# Ring_wearable_ver3_4.net
KiCad netlist of a schematic drawn in Altium Designer
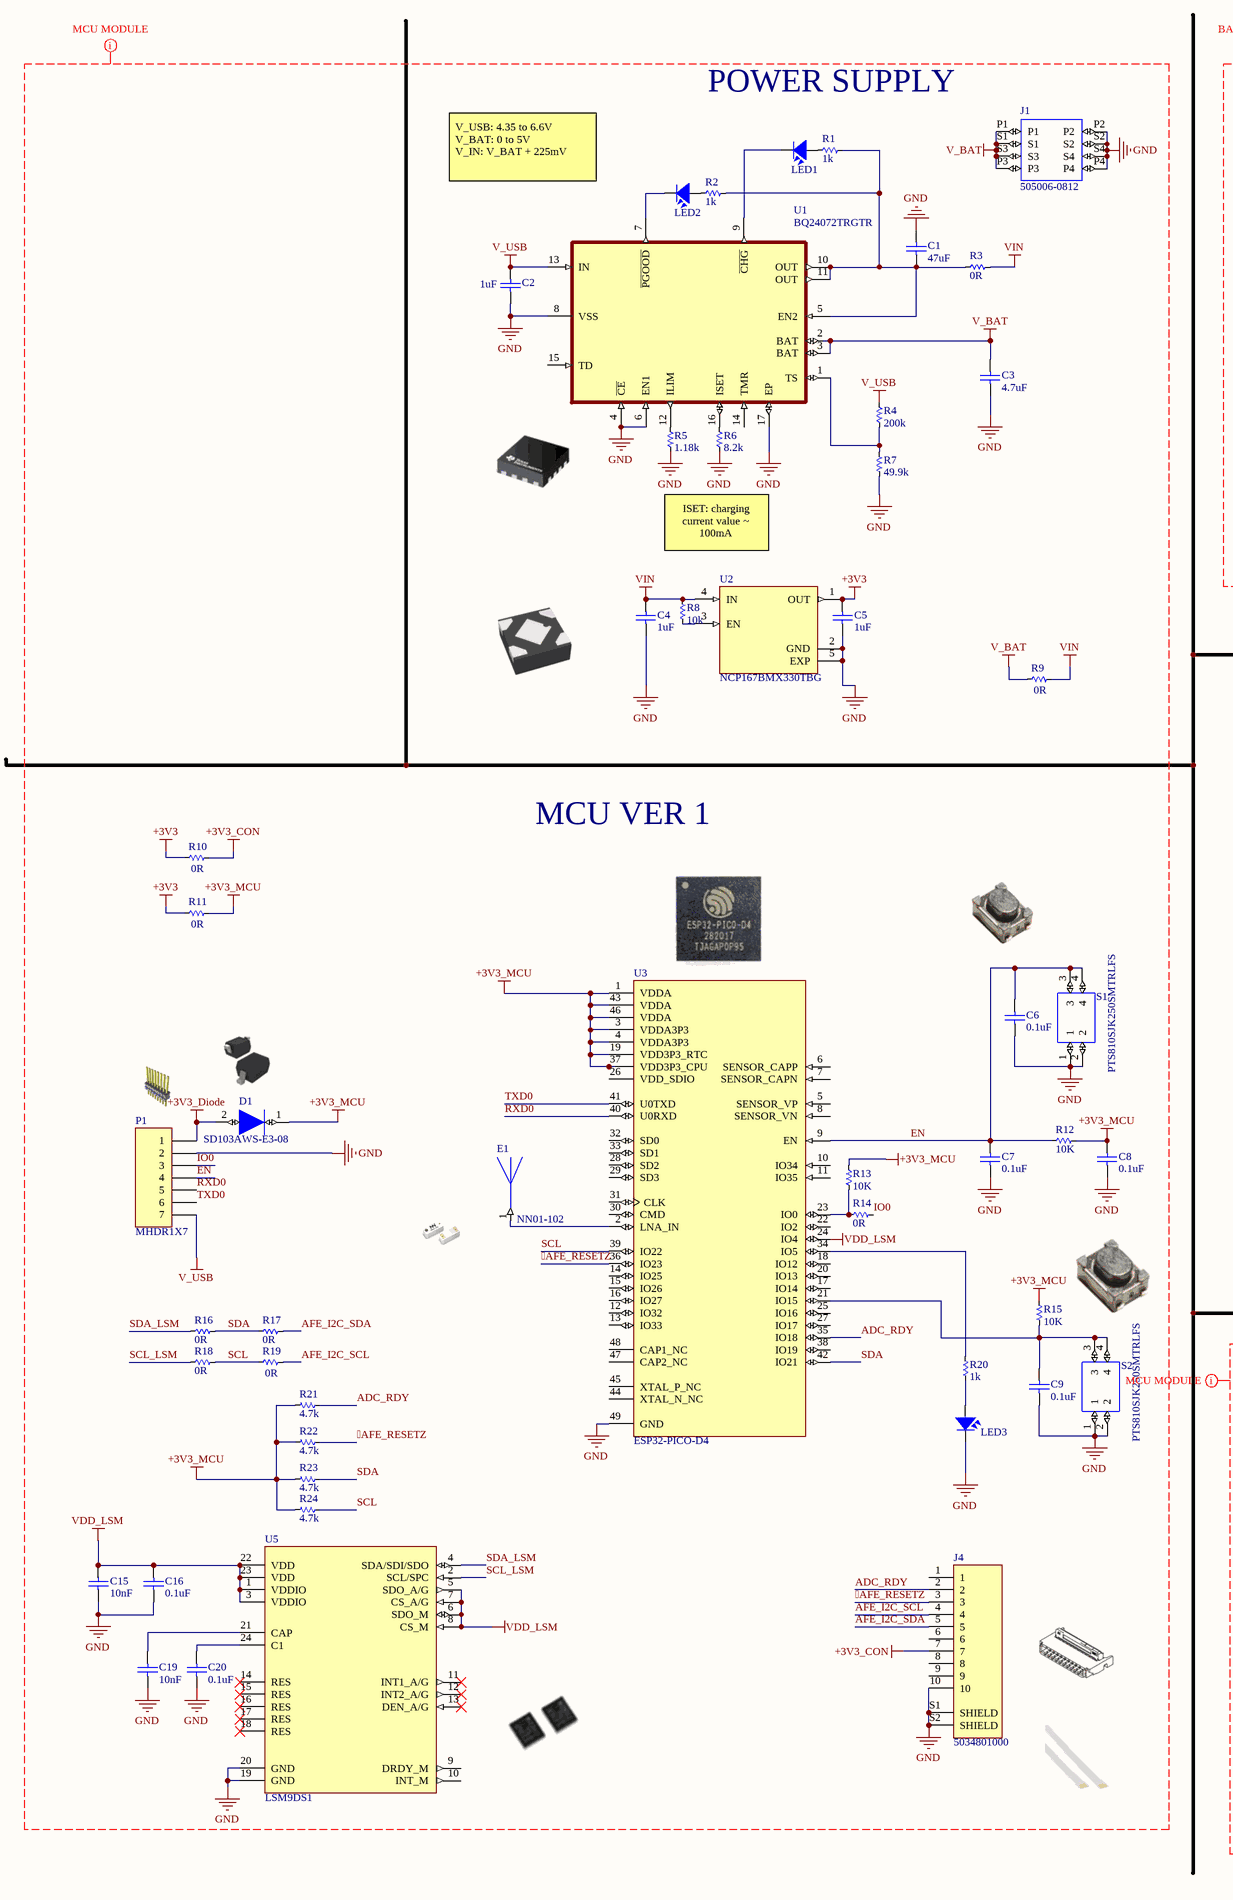
[diagram p0: Ring_wearable_ver3.4.SchDoc, left]
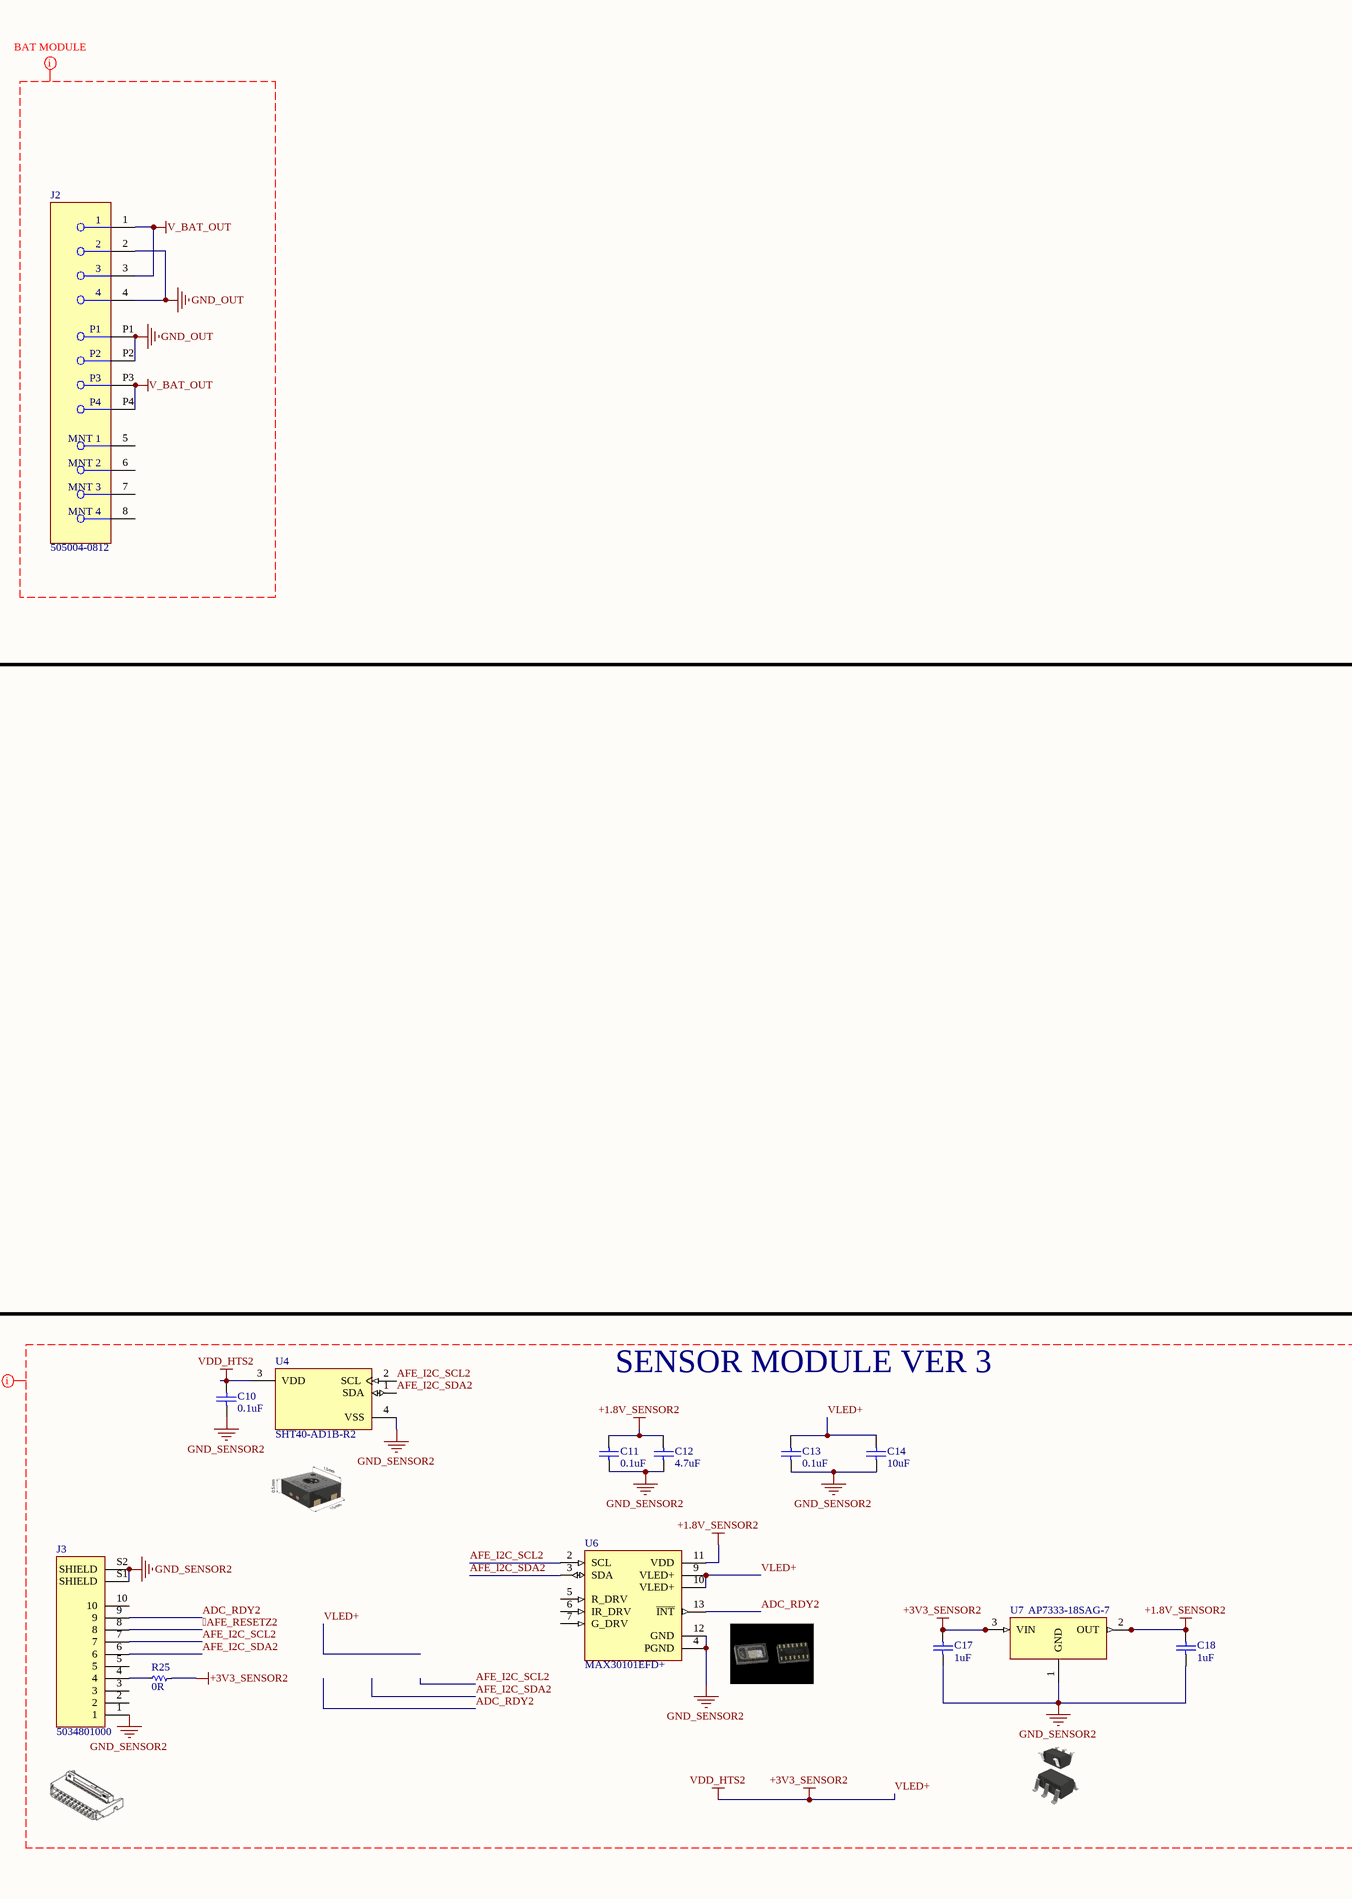
[diagram p1: Ring_wearable_ver3.4.SchDoc, right]

(export (version "E")
  (design (tool "Eeschema 10.0.6"))
  (components
    (comp (ref "C1")
      (value "4.7uF")
      (footprint "RES-SMD-0402")
      (description "Capacitor")
      (fields (field (name "ALTIUM_UNNAMED_1") "47uF") (field (name "PUBLISHER") "Altium Limited"))
      (libsource (lib "Miscellaneous Devices") (part "Cap"))
    )
    (comp (ref "C2")
      (value "1uF")
      (footprint "RES-SMD-0402")
      (description "Capacitor")
      (fields (field (name "ALTIUM_UNNAMED_1") "1uF") (field (name "PUBLISHER") "Altium Limited"))
      (libsource (lib "Miscellaneous Devices") (part "Cap"))
    )
    (comp (ref "C3")
      (value "4.7uF")
      (footprint "RES-SMD-0402")
      (description "Capacitor")
      (fields (field (name "ALTIUM_UNNAMED_1") "4.7uF") (field (name "PUBLISHER") "Altium Limited"))
      (libsource (lib "Miscellaneous Devices") (part "Cap"))
    )
    (comp (ref "C4")
      (value "1uF")
      (footprint "RES-SMD-0402")
      (description "Capacitor")
      (fields (field (name "ALTIUM_UNNAMED_1") "1uF") (field (name "PUBLISHER") "Altium Limited"))
      (libsource (lib "Miscellaneous Devices") (part "Cap"))
    )
    (comp (ref "C5")
      (value "1uF")
      (footprint "RES-SMD-0402")
      (description "Capacitor")
      (fields (field (name "ALTIUM_UNNAMED_1") "1uF") (field (name "PUBLISHER") "Altium Limited"))
      (libsource (lib "Miscellaneous Devices") (part "Cap"))
    )
    (comp (ref "C6")
      (value "0.1uF")
      (footprint "RES-SMD-0402")
      (description "Capacitor")
      (fields (field (name "ALTIUM_UNNAMED_1") "0.1uF") (field (name "PUBLISHER") "Altium Limited"))
      (libsource (lib "Miscellaneous Devices") (part "Cap"))
    )
    (comp (ref "C7")
      (value "0.1uF")
      (footprint "RES-SMD-0603")
      (description "Capacitor")
      (fields (field (name "ALTIUM_UNNAMED_1") "0.1uF") (field (name "PUBLISHER") "Altium Limited"))
      (libsource (lib "Miscellaneous Devices") (part "Cap"))
    )
    (comp (ref "C8")
      (value "0.1uF")
      (footprint "RES-SMD-0402")
      (description "Capacitor")
      (fields (field (name "ALTIUM_UNNAMED_1") "0.1uF") (field (name "PUBLISHER") "Altium Limited"))
      (libsource (lib "Miscellaneous Devices") (part "Cap"))
    )
    (comp (ref "C9")
      (value "0.1uF")
      (footprint "RES-SMD-0402")
      (description "Capacitor")
      (fields (field (name "ALTIUM_UNNAMED_1") "0.1uF") (field (name "PUBLISHER") "Altium Limited"))
      (libsource (lib "Miscellaneous Devices") (part "Cap"))
    )
    (comp (ref "C10")
      (value "0.1uF")
      (footprint "RES-SMD-0402")
      (description "Capacitor")
      (fields (field (name "ALTIUM_UNNAMED_1") "0.1uF") (field (name "PUBLISHER") "Altium Limited"))
      (libsource (lib "Miscellaneous Devices") (part "Cap"))
    )
    (comp (ref "C11")
      (value "0.1uF")
      (footprint "RES-SMD-0402")
      (description "Capacitor")
      (fields (field (name "ALTIUM_UNNAMED_1") "0.1uF") (field (name "PUBLISHER") "Altium Limited"))
      (libsource (lib "Miscellaneous Devices") (part "Cap"))
    )
    (comp (ref "C12")
      (value "4.7uF")
      (footprint "RES-SMD-0402")
      (description "Capacitor")
      (fields (field (name "ALTIUM_UNNAMED_1") "4.7uF") (field (name "PUBLISHER") "Altium Limited"))
      (libsource (lib "Miscellaneous Devices") (part "Cap"))
    )
    (comp (ref "C13")
      (value "0.1uF")
      (footprint "RES-SMD-0402")
      (description "Capacitor")
      (fields (field (name "ALTIUM_UNNAMED_1") "0.1uF") (field (name "PUBLISHER") "Altium Limited"))
      (libsource (lib "Miscellaneous Devices") (part "Cap"))
    )
    (comp (ref "C14")
      (value "10uF")
      (footprint "RES-SMD-0402")
      (description "Capacitor")
      (fields (field (name "ALTIUM_UNNAMED_1") "10uF") (field (name "PUBLISHER") "Altium Limited"))
      (libsource (lib "Miscellaneous Devices") (part "Cap"))
    )
    (comp (ref "C15")
      (value "10nF")
      (footprint "RES-SMD-0402")
      (description "Capacitor")
      (fields (field (name "ALTIUM_UNNAMED_1") "10nF") (field (name "PUBLISHER") "Altium Limited"))
      (libsource (lib "Miscellaneous Devices") (part "Cap"))
    )
    (comp (ref "C16")
      (value "0.1uF")
      (footprint "RES-SMD-0402")
      (description "Capacitor")
      (fields (field (name "ALTIUM_UNNAMED_1") "0.1uF") (field (name "PUBLISHER") "Altium Limited"))
      (libsource (lib "Miscellaneous Devices") (part "Cap"))
    )
    (comp (ref "C17")
      (value "1uF")
      (footprint "RES-SMD-0402")
      (description "Capacitor")
      (fields (field (name "ALTIUM_UNNAMED_1") "1uF") (field (name "PUBLISHER") "Altium Limited"))
      (libsource (lib "Miscellaneous Devices") (part "Cap"))
    )
    (comp (ref "C18")
      (value "1uF")
      (footprint "RES-SMD-0402")
      (description "Capacitor")
      (fields (field (name "ALTIUM_UNNAMED_1") "1uF") (field (name "PUBLISHER") "Altium Limited"))
      (libsource (lib "Miscellaneous Devices") (part "Cap"))
    )
    (comp (ref "C19")
      (value "10nF")
      (footprint "RES-SMD-0402")
      (description "Capacitor")
      (fields (field (name "ALTIUM_UNNAMED_1") "10nF") (field (name "PUBLISHER") "Altium Limited"))
      (libsource (lib "Miscellaneous Devices") (part "Cap"))
    )
    (comp (ref "C20")
      (value "0.1uF")
      (footprint "RES-SMD-0402")
      (description "Capacitor")
      (fields (field (name "ALTIUM_UNNAMED_1") "0.1uF") (field (name "PUBLISHER") "Altium Limited"))
      (libsource (lib "Miscellaneous Devices") (part "Cap"))
    )
    (comp (ref "D1")
      (value "SD103AWS-E3-08")
      (footprint "SOD2713X115N")
      (fields (field (name "MF") "Vishay") (field (name "DIGI-KEY_PART_NUMBER") "SD103AWS-E3-08GITR-ND"))
      (libsource (lib "SD103AWS-E3-08") (part "SD103AWS-E3-08"))
    )
    (comp (ref "E1")
      (value "NN01-102")
      (footprint "XCVR_NN01-102")
      (description "2.45GHz Bluetooth, WLAN, Zigbeeâ„¢ Chip RF Antenna 2.4GHz ~ 2.5GHz 1.7dBi Solder Surface Mount")
      (fields (field (name "MF") "Ignion"))
      (libsource (lib "NN01-102") (part "NN01-102"))
    )
    (comp (ref "J1")
      (value "505006-0812")
      (footprint "5050060812:5050060812")
      (description "8 (4 + 4 Power) Position Connector Plug, Outer Shroud Contacts Surface Mount Gold")
      (fields (field (name "MF") "Molex"))
      (libsource (lib "505006-0812") (part "505006-0812"))
    )
    (comp (ref "J2")
      (value "505004-0812")
      (footprint "FP-505004-0812-MFG")
      (description "CONN RCPT 4POS SMD GOLD")
      (libsource (lib "Altium Content Vault") (part "23163b8db27f5e4a30e89b4e86b5801"))
    )
    (comp (ref "J3")
      (value "5034801000")
      (footprint "MOLEX_5034801000")
      (description "10 Position FFC, FPC Connector Contacts, Top and Bottom 0.020 _0.50mm_ Surface Mount, Right Angle")
      (fields (field (name "MF") "Molex") (field (name "DIGI-KEY_PART_NUMBER") "WM1389CT-ND"))
      (libsource (lib "") (part "5034801000_1"))
    )
    (comp (ref "J4")
      (value "5034801000")
      (footprint "MOLEX_5034801000")
      (description "10 Position FFC, FPC Connector Contacts, Top and Bottom 0.020 _0.50mm_ Surface Mount, Right Angle")
      (fields (field (name "MF") "Molex") (field (name "DIGI-KEY_PART_NUMBER") "WM1389CT-ND"))
      (libsource (lib "5034801000") (part "5034801000"))
    )
    (comp (ref "LED1")
      (value "LED_INDICATE1")
      (footprint "LED-0402")
      (description "LED Single colour Green and Red")
      (libsource (lib "LIBRARY") (part "LED"))
    )
    (comp (ref "LED2")
      (value "LED_INDICATE2")
      (footprint "LED-0402")
      (description "LED Single colour Green and Red")
      (libsource (lib "LIBRARY") (part "LED"))
    )
    (comp (ref "LED3")
      (value "LED_INDICATE3")
      (footprint "LED-0402")
      (description "LED Single colour Green and Red")
      (libsource (lib "LIBRARY") (part "LED"))
    )
    (comp (ref "P1")
      (value "MHDR1X7")
      (footprint "MHDR1X7")
      (description "Header, 7-Pin")
      (fields (field (name "PUBLISHER") "Altium Limited"))
      (libsource (lib "Miscellaneous Connectors") (part "MHDR1X7"))
    )
    (comp (ref "R1")
      (value "1k")
      (footprint "RES-SMD-0402")
      (description "Resistor")
      (fields
        (field (name "MANUFACTURER") "Generic Components")
        (field (name "PUBLISHER") "Altium Hobart Technology Centre")
      )
      (libsource (lib "LIBRARY") (part "Res-SMD"))
    )
    (comp (ref "R2")
      (value "1k")
      (footprint "RES-SMD-0402")
      (description "Resistor")
      (fields
        (field (name "MANUFACTURER") "Generic Components")
        (field (name "PUBLISHER") "Altium Hobart Technology Centre")
      )
      (libsource (lib "LIBRARY") (part "Res-SMD"))
    )
    (comp (ref "R3")
      (value "0R")
      (footprint "RES-SMD-0402")
      (description "Resistor")
      (fields
        (field (name "MANUFACTURER") "Generic Components")
        (field (name "PUBLISHER") "Altium Hobart Technology Centre")
      )
      (libsource (lib "LIBRARY") (part "Res-SMD"))
    )
    (comp (ref "R4")
      (value "200k")
      (footprint "RES-SMD-0402")
      (description "Resistor")
      (fields
        (field (name "MANUFACTURER") "Generic Components")
        (field (name "PUBLISHER") "Altium Hobart Technology Centre")
      )
      (libsource (lib "LIBRARY") (part "Res-SMD"))
    )
    (comp (ref "R5")
      (value "1.18k")
      (footprint "RES-SMD-0402")
      (description "Resistor")
      (fields
        (field (name "MANUFACTURER") "Generic Components")
        (field (name "PUBLISHER") "Altium Hobart Technology Centre")
      )
      (libsource (lib "LIBRARY") (part "Res-SMD"))
    )
    (comp (ref "R6")
      (value "8.2k")
      (footprint "RES-SMD-0402")
      (description "Resistor")
      (fields
        (field (name "MANUFACTURER") "Generic Components")
        (field (name "PUBLISHER") "Altium Hobart Technology Centre")
      )
      (libsource (lib "LIBRARY") (part "Res-SMD"))
    )
    (comp (ref "R7")
      (value "49.9k")
      (footprint "RES-SMD-0402")
      (description "Resistor")
      (fields
        (field (name "MANUFACTURER") "Generic Components")
        (field (name "PUBLISHER") "Altium Hobart Technology Centre")
      )
      (libsource (lib "LIBRARY") (part "Res-SMD"))
    )
    (comp (ref "R8")
      (value "10k")
      (footprint "RES-SMD-0402")
      (description "Resistor")
      (fields
        (field (name "MANUFACTURER") "Generic Components")
        (field (name "PUBLISHER") "Altium Hobart Technology Centre")
      )
      (libsource (lib "LIBRARY") (part "Res-SMD"))
    )
    (comp (ref "R9")
      (value "0R")
      (footprint "RES-SMD-0402")
      (description "Resistor")
      (fields
        (field (name "MANUFACTURER") "Generic Components")
        (field (name "PUBLISHER") "Altium Hobart Technology Centre")
      )
      (libsource (lib "LIBRARY") (part "Res-SMD"))
    )
    (comp (ref "R10")
      (value "0R")
      (footprint "RES-SMD-0402")
      (description "Resistor")
      (fields
        (field (name "MANUFACTURER") "Generic Components")
        (field (name "PUBLISHER") "Altium Hobart Technology Centre")
      )
      (libsource (lib "LIBRARY") (part "Res-SMD"))
    )
    (comp (ref "R11")
      (value "0R")
      (footprint "RES-SMD-0402")
      (description "Resistor")
      (fields
        (field (name "MANUFACTURER") "Generic Components")
        (field (name "PUBLISHER") "Altium Hobart Technology Centre")
      )
      (libsource (lib "LIBRARY") (part "Res-SMD"))
    )
    (comp (ref "R12")
      (value "10K")
      (footprint "RES-SMD-0402")
      (description "Resistor")
      (fields
        (field (name "MANUFACTURER") "Generic Components")
        (field (name "PUBLISHER") "Altium Hobart Technology Centre")
      )
      (libsource (lib "LIBRARY") (part "Res-SMD"))
    )
    (comp (ref "R13")
      (value "10K")
      (footprint "RES-SMD-0603")
      (description "Resistor")
      (fields
        (field (name "MANUFACTURER") "Generic Components")
        (field (name "PUBLISHER") "Altium Hobart Technology Centre")
      )
      (libsource (lib "LIBRARY") (part "Res-SMD"))
    )
    (comp (ref "R14")
      (value "0R")
      (footprint "RES-SMD-0603")
      (description "Resistor")
      (fields
        (field (name "MANUFACTURER") "Generic Components")
        (field (name "PUBLISHER") "Altium Hobart Technology Centre")
      )
      (libsource (lib "LIBRARY") (part "Res-SMD"))
    )
    (comp (ref "R15")
      (value "10K")
      (footprint "RES-SMD-0402")
      (description "Resistor")
      (fields
        (field (name "MANUFACTURER") "Generic Components")
        (field (name "PUBLISHER") "Altium Hobart Technology Centre")
      )
      (libsource (lib "LIBRARY") (part "Res-SMD"))
    )
    (comp (ref "R16")
      (value "0R")
      (footprint "RES-SMD-0402")
      (description "Resistor")
      (fields
        (field (name "MANUFACTURER") "Generic Components")
        (field (name "PUBLISHER") "Altium Hobart Technology Centre")
      )
      (libsource (lib "LIBRARY") (part "Res-SMD"))
    )
    (comp (ref "R17")
      (value "0R")
      (footprint "RES-SMD-0402")
      (description "Resistor")
      (fields
        (field (name "MANUFACTURER") "Generic Components")
        (field (name "PUBLISHER") "Altium Hobart Technology Centre")
      )
      (libsource (lib "LIBRARY") (part "Res-SMD"))
    )
    (comp (ref "R18")
      (value "0R")
      (footprint "RES-SMD-0402")
      (description "Resistor")
      (fields
        (field (name "MANUFACTURER") "Generic Components")
        (field (name "PUBLISHER") "Altium Hobart Technology Centre")
      )
      (libsource (lib "LIBRARY") (part "Res-SMD"))
    )
    (comp (ref "R19")
      (value "0R")
      (footprint "RES-SMD-0402")
      (description "Resistor")
      (fields
        (field (name "MANUFACTURER") "Generic Components")
        (field (name "PUBLISHER") "Altium Hobart Technology Centre")
      )
      (libsource (lib "LIBRARY") (part "Res-SMD"))
    )
    (comp (ref "R20")
      (value "1k")
      (footprint "RES-SMD-0402")
      (description "Resistor")
      (fields
        (field (name "MANUFACTURER") "Generic Components")
        (field (name "PUBLISHER") "Altium Hobart Technology Centre")
      )
      (libsource (lib "LIBRARY") (part "Res-SMD"))
    )
    (comp (ref "R21")
      (value "4.7k")
      (footprint "RES-SMD-0402")
      (description "Resistor")
      (fields
        (field (name "MANUFACTURER") "Generic Components")
        (field (name "PUBLISHER") "Altium Hobart Technology Centre")
      )
      (libsource (lib "LIBRARY") (part "Res-SMD"))
    )
    (comp (ref "R22")
      (value "4.7k")
      (footprint "RES-SMD-0402")
      (description "Resistor")
      (fields
        (field (name "MANUFACTURER") "Generic Components")
        (field (name "PUBLISHER") "Altium Hobart Technology Centre")
      )
      (libsource (lib "LIBRARY") (part "Res-SMD"))
    )
    (comp (ref "R23")
      (value "4.7k")
      (footprint "RES-SMD-0402")
      (description "Resistor")
      (fields
        (field (name "MANUFACTURER") "Generic Components")
        (field (name "PUBLISHER") "Altium Hobart Technology Centre")
      )
      (libsource (lib "LIBRARY") (part "Res-SMD"))
    )
    (comp (ref "R24")
      (value "4.7k")
      (footprint "RES-SMD-0402")
      (description "Resistor")
      (fields
        (field (name "MANUFACTURER") "Generic Components")
        (field (name "PUBLISHER") "Altium Hobart Technology Centre")
      )
      (libsource (lib "LIBRARY") (part "Res-SMD"))
    )
    (comp (ref "R25")
      (value "0R")
      (footprint "RES-SMD-0402")
      (description "Resistor")
      (fields
        (field (name "MANUFACTURER") "Generic Components")
        (field (name "PUBLISHER") "Altium Hobart Technology Centre")
      )
      (libsource (lib "LIBRARY") (part "Res-SMD"))
    )
    (comp (ref "S1")
      (value "PTS810SJK250SMTRLFS")
      (footprint "PTS810SJG250SMTRLFS")
      (description "Tactile Switch SPST-NO Top Actuated Surface Mount")
      (fields (field (name "MF") "C&K"))
      (libsource (lib "PTS810SJK250SMTRLFS") (part "PTS810SJK250SMTRLFS"))
    )
    (comp (ref "S2")
      (value "PTS810SJK250SMTRLFS")
      (footprint "PTS810SJG250SMTRLFS")
      (description "Tactile Switch SPST-NO Top Actuated Surface Mount")
      (fields (field (name "MF") "C&K"))
      (libsource (lib "PTS810SJK250SMTRLFS") (part "PTS810SJK250SMTRLFS"))
    )
    (comp (ref "U1")
      (value "BQ24072TRGTR")
      (footprint "QFN50P300X300X100-17N")
      (fields (field (name "MF") "Texas Instruments"))
      (libsource (lib "BQ24072TRGTR") (part "BQ24072TRGTR"))
    )
    (comp (ref "U2")
      (value "NCP167BMX330TBG")
      (footprint "REG_NCP167BMX330TBG")
      (description "Linear Voltage Regulator IC 1 Output 700mA 4-XDFN _1x1_")
      (fields
        (field (name "DIGI-KEY_PART_NUMBER") "NCP167BMX330TBGOSCT-ND")
        (field (name "MF") "ON Semiconductor")
      )
      (libsource (lib "NCP167BMX330TBG") (part "NCP167BMX330TBG"))
    )
    (comp (ref "U3")
      (value "ESP32-PICO-D4")
      (footprint "PQFN50P700X700X104-49N")
      (libsource (lib "ESP32-PICO-D4") (part "ESP32-PICO-D4"))
    )
    (comp (ref "U4")
      (value "SHT40-AD1B-R2")
      (footprint "FP-SHT40-AD1B-R2-MFG")
      (description "SENSOR HUMIDITY 100 RH SMD")
      (libsource (lib "Altium Content Vault") (part "985d6b895d3abb4f56b1b691ea450a8"))
    )
    (comp (ref "U5")
      (value "LSM9DS1")
      (footprint "PQFN24P43_350X300X102L35X23N")
      (description "Accelerometer, Gyroscope, Magnetometer, Temperature, 9 Axis Sensor IÂ²C, SPI Output")
      (fields (field (name "MF") "STMicroelectronics"))
      (libsource (lib "LSM9DS1") (part "LSM9DS1"))
    )
    (comp (ref "U6")
      (value "MAX30101EFD+")
      (footprint "PSON80P330X560X165-14N")
      (description "Oximeter/Heart Rate Sensor IÂ²C Output")
      (fields (field (name "MF") "Maxim Integrated"))
      (libsource (lib "MAX30101EFD_") (part "MAX30101EFD+"))
    )
    (comp (ref "U7")
      (value "AP7333-18SAG-7")
      (footprint "SOT23-132")
      (libsource (lib "LIBRARY") (part "AP7370-18SA-7"))
    )
  )
  (nets
    (net (code "1") (name "+1.8V_SENSOR2") (class "Default")
      (node (ref "C11") (pin "1") (pinfunction "1_1") (pintype "passive"))
      (node (ref "C12") (pin "1") (pinfunction "1_1") (pintype "passive"))
      (node (ref "C18") (pin "1") (pinfunction "1_1") (pintype "passive"))
      (node (ref "U6") (pin "11") (pinfunction "VDD_11") (pintype "power_in"))
      (node (ref "U7") (pin "2") (pinfunction "OUT_2") (pintype "output"))
    )
    (net (code "2") (name "+3V3") (class "Default")
      (node (ref "C5") (pin "1") (pinfunction "1_1") (pintype "passive"))
      (node (ref "R10") (pin "2") (pinfunction "2_2") (pintype "passive"))
      (node (ref "R11") (pin "2") (pinfunction "2_2") (pintype "passive"))
      (node (ref "U2") (pin "1") (pinfunction "OUT_1") (pintype "output"))
    )
    (net (code "3") (name "+3V3_CON") (class "Default")
      (node (ref "J4") (pin "7") (pinfunction "7_7") (pintype "passive"))
      (node (ref "R10") (pin "1") (pinfunction "1_1") (pintype "passive"))
    )
    (net (code "4") (name "+3V3_Diode") (class "Default")
      (node (ref "D1") (pin "2") (pinfunction "A_2") (pintype "bidirectional"))
      (node (ref "P1") (pin "1") (pinfunction "1_1") (pintype "passive"))
    )
    (net (code "5") (name "+3V3_MCU") (class "Default")
      (node (ref "C8") (pin "1") (pinfunction "1_1") (pintype "passive"))
      (node (ref "D1") (pin "1") (pinfunction "K_1") (pintype "bidirectional"))
      (node (ref "R11") (pin "1") (pinfunction "1_1") (pintype "passive"))
      (node (ref "R12") (pin "1") (pinfunction "1_1") (pintype "passive"))
      (node (ref "R13") (pin "1") (pinfunction "1_1") (pintype "passive"))
      (node (ref "R15") (pin "1") (pinfunction "1_1") (pintype "passive"))
      (node (ref "R21") (pin "1") (pinfunction "1_1") (pintype "passive"))
      (node (ref "R22") (pin "1") (pinfunction "1_1") (pintype "passive"))
      (node (ref "R23") (pin "1") (pinfunction "1_1") (pintype "passive"))
      (node (ref "R24") (pin "1") (pinfunction "1_1") (pintype "passive"))
      (node (ref "U3") (pin "1") (pinfunction "VDDA_1") (pintype "power_in"))
      (node (ref "U3") (pin "19") (pinfunction "VDD3P3_RTC_19") (pintype "power_in"))
      (node (ref "U3") (pin "3") (pinfunction "VDDA3P3_3") (pintype "power_in"))
      (node (ref "U3") (pin "37") (pinfunction "VDD3P3_CPU_37") (pintype "power_in"))
      (node (ref "U3") (pin "4") (pinfunction "VDDA3P3_4") (pintype "power_in"))
      (node (ref "U3") (pin "43") (pinfunction "VDDA_43") (pintype "power_in"))
      (node (ref "U3") (pin "46") (pinfunction "VDDA_46") (pintype "power_in"))
    )
    (net (code "6") (name "+3V3_SENSOR2") (class "Default")
      (node (ref "C10") (pin "1") (pinfunction "1_1") (pintype "passive"))
      (node (ref "C13") (pin "1") (pinfunction "1_1") (pintype "passive"))
      (node (ref "C14") (pin "1") (pinfunction "1_1") (pintype "passive"))
      (node (ref "C17") (pin "1") (pinfunction "1_1") (pintype "passive"))
      (node (ref "R25") (pin "1") (pinfunction "1_1") (pintype "passive"))
      (node (ref "U4") (pin "3") (pinfunction "VDD_3") (pintype "power_in"))
      (node (ref "U6") (pin "10") (pinfunction "VLED+_10") (pintype "power_in"))
      (node (ref "U6") (pin "9") (pinfunction "VLED+_9") (pintype "power_in"))
      (node (ref "U7") (pin "3") (pinfunction "VIN_3") (pintype "input"))
    )
    (net (code "7") (name "/AFE_RESETZ") (class "Default")
      (node (ref "J4") (pin "3") (pinfunction "3_3") (pintype "passive"))
      (node (ref "R22") (pin "2") (pinfunction "2_2") (pintype "passive"))
      (node (ref "U3") (pin "36") (pinfunction "IO23_36") (pintype "bidirectional"))
    )
    (net (code "8") (name "/AFE_RESETZ2") (class "Default")
      (node (ref "J3") (pin "8") (pinfunction "8_8") (pintype "passive"))
    )
    (net (code "9") (name "/ADC_RDY") (class "Default")
      (node (ref "J4") (pin "2") (pinfunction "2_2") (pintype "passive"))
      (node (ref "R21") (pin "2") (pinfunction "2_2") (pintype "passive"))
      (node (ref "U3") (pin "35") (pinfunction "IO18_35") (pintype "bidirectional"))
    )
    (net (code "10") (name "/ADC_RDY2") (class "Default")
      (node (ref "J3") (pin "9") (pinfunction "9_9") (pintype "passive"))
      (node (ref "U6") (pin "13") (pinfunction "~{INT}_13") (pintype "output"))
    )
    (net (code "11") (name "/AFE_I2C_SCL") (class "Default")
      (node (ref "J4") (pin "4") (pinfunction "4_4") (pintype "passive"))
      (node (ref "R19") (pin "1") (pinfunction "1_1") (pintype "passive"))
    )
    (net (code "12") (name "/AFE_I2C_SCL2") (class "Default")
      (node (ref "J3") (pin "7") (pinfunction "7_7") (pintype "passive"))
      (node (ref "U4") (pin "2") (pinfunction "SCL_2") (pintype "input"))
      (node (ref "U6") (pin "2") (pinfunction "SCL_2") (pintype "input"))
    )
    (net (code "13") (name "/AFE_I2C_SDA") (class "Default")
      (node (ref "J4") (pin "5") (pinfunction "5_5") (pintype "passive"))
      (node (ref "R17") (pin "1") (pinfunction "1_1") (pintype "passive"))
    )
    (net (code "14") (name "/AFE_I2C_SDA2") (class "Default")
      (node (ref "J3") (pin "6") (pinfunction "6_6") (pintype "passive"))
      (node (ref "U4") (pin "1") (pinfunction "SDA_1") (pintype "bidirectional"))
      (node (ref "U6") (pin "3") (pinfunction "SDA_3") (pintype "bidirectional"))
    )
    (net (code "15") (name "/EN") (class "Default")
      (node (ref "C6") (pin "1") (pinfunction "1_1") (pintype "passive"))
      (node (ref "C7") (pin "1") (pinfunction "1_1") (pintype "passive"))
      (node (ref "P1") (pin "4") (pinfunction "4_4") (pintype "passive"))
      (node (ref "R12") (pin "2") (pinfunction "2_2") (pintype "passive"))
      (node (ref "S1") (pin "3") (pinfunction "3_3") (pintype "bidirectional"))
      (node (ref "S1") (pin "4") (pinfunction "4_4") (pintype "bidirectional"))
      (node (ref "U3") (pin "9") (pinfunction "EN_9") (pintype "input"))
    )
    (net (code "16") (name "/IO0") (class "Default")
      (node (ref "P1") (pin "3") (pinfunction "3_3") (pintype "passive"))
      (node (ref "R14") (pin "1") (pinfunction "1_1") (pintype "passive"))
    )
    (net (code "17") (name "/RXD0") (class "Default")
      (node (ref "P1") (pin "5") (pinfunction "5_5") (pintype "passive"))
      (node (ref "U3") (pin "40") (pinfunction "U0RXD_40") (pintype "bidirectional"))
    )
    (net (code "18") (name "/SCL") (class "Default")
      (node (ref "R18") (pin "1") (pinfunction "1_1") (pintype "passive"))
      (node (ref "R19") (pin "2") (pinfunction "2_2") (pintype "passive"))
      (node (ref "R24") (pin "2") (pinfunction "2_2") (pintype "passive"))
      (node (ref "U3") (pin "39") (pinfunction "IO22_39") (pintype "bidirectional"))
    )
    (net (code "19") (name "/SCL_LSM") (class "Default")
      (node (ref "R18") (pin "2") (pinfunction "2_2") (pintype "passive"))
      (node (ref "U5") (pin "2") (pinfunction "SCL/SPC_2") (pintype "input"))
    )
    (net (code "20") (name "/SDA") (class "Default")
      (node (ref "R16") (pin "1") (pinfunction "1_1") (pintype "passive"))
      (node (ref "R17") (pin "2") (pinfunction "2_2") (pintype "passive"))
      (node (ref "R23") (pin "2") (pinfunction "2_2") (pintype "passive"))
      (node (ref "U3") (pin "42") (pinfunction "IO21_42") (pintype "bidirectional"))
    )
    (net (code "21") (name "/SDA_LSM") (class "Default")
      (node (ref "R16") (pin "2") (pinfunction "2_2") (pintype "passive"))
      (node (ref "U5") (pin "4") (pinfunction "SDA/SDI/SDO_4") (pintype "bidirectional"))
    )
    (net (code "22") (name "/TXD0") (class "Default")
      (node (ref "P1") (pin "6") (pinfunction "6_6") (pintype "passive"))
      (node (ref "U3") (pin "41") (pinfunction "U0TXD_41") (pintype "bidirectional"))
    )
    (net (code "23") (name "GND") (class "Default")
      (node (ref "C1") (pin "1") (pinfunction "1_1") (pintype "passive"))
      (node (ref "C15") (pin "2") (pinfunction "2_2") (pintype "passive"))
      (node (ref "C16") (pin "2") (pinfunction "2_2") (pintype "passive"))
      (node (ref "C19") (pin "2") (pinfunction "2_2") (pintype "passive"))
      (node (ref "C2") (pin "1") (pinfunction "1_1") (pintype "passive"))
      (node (ref "C20") (pin "2") (pinfunction "2_2") (pintype "passive"))
      (node (ref "C3") (pin "2") (pinfunction "2_2") (pintype "passive"))
      (node (ref "C4") (pin "2") (pinfunction "2_2") (pintype "passive"))
      (node (ref "C5") (pin "2") (pinfunction "2_2") (pintype "passive"))
      (node (ref "C6") (pin "2") (pinfunction "2_2") (pintype "passive"))
      (node (ref "C7") (pin "2") (pinfunction "2_2") (pintype "passive"))
      (node (ref "C8") (pin "2") (pinfunction "2_2") (pintype "passive"))
      (node (ref "C9") (pin "2") (pinfunction "2_2") (pintype "passive"))
      (node (ref "J1") (pin "P2") (pinfunction "P2_P2") (pintype "bidirectional"))
      (node (ref "J1") (pin "P4") (pinfunction "P4_P4") (pintype "bidirectional"))
      (node (ref "J1") (pin "S2") (pinfunction "S2_S2") (pintype "bidirectional"))
      (node (ref "J1") (pin "S4") (pinfunction "S4_S4") (pintype "bidirectional"))
      (node (ref "J4") (pin "10") (pinfunction "10_10") (pintype "passive"))
      (node (ref "J4") (pin "S1") (pinfunction "SHIELD_S1") (pintype "passive"))
      (node (ref "J4") (pin "S2") (pinfunction "SHIELD_S2") (pintype "passive"))
      (node (ref "LED3") (pin "2") (pinfunction "2_2") (pintype "passive"))
      (node (ref "P1") (pin "2") (pinfunction "2_2") (pintype "passive"))
      (node (ref "R5") (pin "1") (pinfunction "1_1") (pintype "passive"))
      (node (ref "R6") (pin "1") (pinfunction "1_1") (pintype "passive"))
      (node (ref "R7") (pin "1") (pinfunction "1_1") (pintype "passive"))
      (node (ref "S1") (pin "1") (pinfunction "1_1") (pintype "bidirectional"))
      (node (ref "S1") (pin "2") (pinfunction "2_2") (pintype "bidirectional"))
      (node (ref "S2") (pin "1") (pinfunction "1_1") (pintype "bidirectional"))
      (node (ref "S2") (pin "2") (pinfunction "2_2") (pintype "bidirectional"))
      (node (ref "U1") (pin "17") (pinfunction "EP_17") (pintype "bidirectional"))
      (node (ref "U1") (pin "4") (pinfunction "~{CE}_4") (pintype "input"))
      (node (ref "U1") (pin "6") (pinfunction "EN1_6") (pintype "input"))
      (node (ref "U1") (pin "8") (pinfunction "VSS_8") (pintype "power_in"))
      (node (ref "U2") (pin "2") (pinfunction "GND_2") (pintype "power_in"))
      (node (ref "U2") (pin "5") (pinfunction "EXP_5") (pintype "power_in"))
      (node (ref "U3") (pin "49") (pinfunction "GND_49") (pintype "power_in"))
      (node (ref "U5") (pin "19") (pinfunction "GND_19") (pintype "power_in"))
      (node (ref "U5") (pin "20") (pinfunction "GND_20") (pintype "power_in"))
    )
    (net (code "24") (name "GND_OUT") (class "Default")
      (node (ref "J2") (pin "2") (pinfunction "2_2") (pintype "passive"))
      (node (ref "J2") (pin "4") (pinfunction "4_4") (pintype "passive"))
      (node (ref "J2") (pin "P1") (pinfunction "P1_P1") (pintype "passive"))
      (node (ref "J2") (pin "P2") (pinfunction "P2_P2") (pintype "passive"))
    )
    (net (code "25") (name "GND_SENSOR2") (class "Default")
      (node (ref "C10") (pin "2") (pinfunction "2_2") (pintype "passive"))
      (node (ref "C11") (pin "2") (pinfunction "2_2") (pintype "passive"))
      (node (ref "C12") (pin "2") (pinfunction "2_2") (pintype "passive"))
      (node (ref "C13") (pin "2") (pinfunction "2_2") (pintype "passive"))
      (node (ref "C14") (pin "2") (pinfunction "2_2") (pintype "passive"))
      (node (ref "C17") (pin "2") (pinfunction "2_2") (pintype "passive"))
      (node (ref "C18") (pin "2") (pinfunction "2_2") (pintype "passive"))
      (node (ref "J3") (pin "1") (pinfunction "1_1") (pintype "passive"))
      (node (ref "J3") (pin "S1") (pinfunction "SHIELD_S1") (pintype "passive"))
      (node (ref "J3") (pin "S2") (pinfunction "SHIELD_S2") (pintype "passive"))
      (node (ref "U4") (pin "4") (pinfunction "VSS_4") (pintype "power_in"))
      (node (ref "U6") (pin "12") (pinfunction "GND_12") (pintype "power_in"))
      (node (ref "U6") (pin "4") (pinfunction "PGND_4") (pintype "power_in"))
      (node (ref "U7") (pin "1") (pinfunction "GND_1") (pintype "power_in"))
    )
    (net (code "26") (name "Net-(J3-Pad4)") (class "Default")
      (node (ref "J3") (pin "4") (pinfunction "4_4") (pintype "passive"))
      (node (ref "R25") (pin "2") (pinfunction "2_2") (pintype "passive"))
    )
    (net (code "27") (name "Net-(LED1-Pad1)") (class "Default")
      (node (ref "LED1") (pin "1") (pinfunction "1_1") (pintype "passive"))
      (node (ref "R1") (pin "2") (pinfunction "2_2") (pintype "passive"))
    )
    (net (code "28") (name "Net-(LED2-Pad1)") (class "Default")
      (node (ref "LED2") (pin "1") (pinfunction "1_1") (pintype "passive"))
      (node (ref "R2") (pin "2") (pinfunction "2_2") (pintype "passive"))
    )
    (net (code "29") (name "Net-(LED3-Pad1)") (class "Default")
      (node (ref "LED3") (pin "1") (pinfunction "1_1") (pintype "passive"))
      (node (ref "R20") (pin "2") (pinfunction "2_2") (pintype "passive"))
    )
    (net (code "30") (name "Net-(U1-EN2)") (class "Default")
      (node (ref "C1") (pin "2") (pinfunction "2_2") (pintype "passive"))
      (node (ref "R1") (pin "1") (pinfunction "1_1") (pintype "passive"))
      (node (ref "R2") (pin "1") (pinfunction "1_1") (pintype "passive"))
      (node (ref "R3") (pin "2") (pinfunction "2_2") (pintype "passive"))
      (node (ref "U1") (pin "10") (pinfunction "OUT_10") (pintype "output"))
      (node (ref "U1") (pin "11") (pinfunction "OUT_11") (pintype "output"))
      (node (ref "U1") (pin "5") (pinfunction "EN2_5") (pintype "input"))
    )
    (net (code "31") (name "Net-(U1-ILIM)") (class "Default")
      (node (ref "R5") (pin "2") (pinfunction "2_2") (pintype "passive"))
      (node (ref "U1") (pin "12") (pinfunction "ILIM_12") (pintype "output"))
    )
    (net (code "32") (name "Net-(U1-ISET)") (class "Default")
      (node (ref "R6") (pin "2") (pinfunction "2_2") (pintype "passive"))
      (node (ref "U1") (pin "16") (pinfunction "ISET_16") (pintype "bidirectional"))
    )
    (net (code "33") (name "Net-(U1-TS)") (class "Default")
      (node (ref "R4") (pin "1") (pinfunction "1_1") (pintype "passive"))
      (node (ref "R7") (pin "2") (pinfunction "2_2") (pintype "passive"))
      (node (ref "U1") (pin "1") (pinfunction "TS_1") (pintype "bidirectional"))
    )
    (net (code "34") (name "Net-(U1-~{CHG})") (class "Default")
      (node (ref "LED1") (pin "2") (pinfunction "2_2") (pintype "passive"))
      (node (ref "U1") (pin "9") (pinfunction "~{CHG}_9") (pintype "output"))
    )
    (net (code "35") (name "Net-(U1-~{PGOOD})") (class "Default")
      (node (ref "LED2") (pin "2") (pinfunction "2_2") (pintype "passive"))
      (node (ref "U1") (pin "7") (pinfunction "~{PGOOD}_7") (pintype "output"))
    )
    (net (code "36") (name "Net-(U2-EN)") (class "Default")
      (node (ref "R8") (pin "1") (pinfunction "1_1") (pintype "passive"))
      (node (ref "U2") (pin "3") (pinfunction "EN_3") (pintype "input"))
    )
    (net (code "37") (name "Net-(U3-IO0)") (class "Default")
      (node (ref "R13") (pin "2") (pinfunction "2_2") (pintype "passive"))
      (node (ref "R14") (pin "2") (pinfunction "2_2") (pintype "passive"))
      (node (ref "U3") (pin "23") (pinfunction "IO0_23") (pintype "bidirectional"))
    )
    (net (code "38") (name "Net-(U3-IO5)") (class "Default")
      (node (ref "R20") (pin "1") (pinfunction "1_1") (pintype "passive"))
      (node (ref "U3") (pin "34") (pinfunction "IO5_34") (pintype "bidirectional"))
    )
    (net (code "39") (name "Net-(U3-IO15)") (class "Default")
      (node (ref "C9") (pin "1") (pinfunction "1_1") (pintype "passive"))
      (node (ref "R15") (pin "2") (pinfunction "2_2") (pintype "passive"))
      (node (ref "S2") (pin "3") (pinfunction "3_3") (pintype "bidirectional"))
      (node (ref "S2") (pin "4") (pinfunction "4_4") (pintype "bidirectional"))
      (node (ref "U3") (pin "21") (pinfunction "IO15_21") (pintype "bidirectional"))
    )
    (net (code "40") (name "Net-(U3-LNA_IN)") (class "Default")
      (node (ref "E1") (pin "1") (pinfunction "1_1") (pintype "input"))
      (node (ref "U3") (pin "2") (pinfunction "LNA_IN_2") (pintype "bidirectional"))
    )
    (net (code "41") (name "Net-(U5-C1)") (class "Default")
      (node (ref "C20") (pin "1") (pinfunction "1_1") (pintype "passive"))
      (node (ref "U5") (pin "24") (pinfunction "C1_24") (pintype "passive"))
    )
    (net (code "42") (name "Net-(U5-CAP)") (class "Default")
      (node (ref "C19") (pin "1") (pinfunction "1_1") (pintype "passive"))
      (node (ref "U5") (pin "21") (pinfunction "CAP_21") (pintype "passive"))
    )
    (net (code "43") (name "VDD_LSM") (class "Default")
      (node (ref "C15") (pin "1") (pinfunction "1_1") (pintype "passive"))
      (node (ref "C16") (pin "1") (pinfunction "1_1") (pintype "passive"))
      (node (ref "U3") (pin "24") (pinfunction "IO4_24") (pintype "bidirectional"))
      (node (ref "U5") (pin "1") (pinfunction "VDDIO_1") (pintype "power_in"))
      (node (ref "U5") (pin "22") (pinfunction "VDD_22") (pintype "power_in"))
      (node (ref "U5") (pin "23") (pinfunction "VDD_23") (pintype "power_in"))
      (node (ref "U5") (pin "3") (pinfunction "VDDIO_3") (pintype "power_in"))
      (node (ref "U5") (pin "5") (pinfunction "SDO_A/G_5") (pintype "output"))
      (node (ref "U5") (pin "6") (pinfunction "SDO_M_6") (pintype "bidirectional"))
      (node (ref "U5") (pin "7") (pinfunction "CS_A/G_7") (pintype "input"))
      (node (ref "U5") (pin "8") (pinfunction "CS_M_8") (pintype "input"))
    )
    (net (code "44") (name "VIN") (class "Default")
      (node (ref "C4") (pin "1") (pinfunction "1_1") (pintype "passive"))
      (node (ref "R3") (pin "1") (pinfunction "1_1") (pintype "passive"))
      (node (ref "R8") (pin "2") (pinfunction "2_2") (pintype "passive"))
      (node (ref "R9") (pin "1") (pinfunction "1_1") (pintype "passive"))
      (node (ref "U2") (pin "4") (pinfunction "IN_4") (pintype "input"))
    )
    (net (code "45") (name "V_BAT") (class "Default")
      (node (ref "C3") (pin "1") (pinfunction "1_1") (pintype "passive"))
      (node (ref "J1") (pin "P1") (pinfunction "P1_P1") (pintype "bidirectional"))
      (node (ref "J1") (pin "P3") (pinfunction "P3_P3") (pintype "bidirectional"))
      (node (ref "J1") (pin "S1") (pinfunction "S1_S1") (pintype "bidirectional"))
      (node (ref "J1") (pin "S3") (pinfunction "S3_S3") (pintype "bidirectional"))
      (node (ref "R9") (pin "2") (pinfunction "2_2") (pintype "passive"))
      (node (ref "U1") (pin "2") (pinfunction "BAT_2") (pintype "bidirectional"))
      (node (ref "U1") (pin "3") (pinfunction "BAT_3") (pintype "bidirectional"))
    )
    (net (code "46") (name "V_BAT_OUT") (class "Default")
      (node (ref "J2") (pin "1") (pinfunction "1_1") (pintype "passive"))
      (node (ref "J2") (pin "3") (pinfunction "3_3") (pintype "passive"))
      (node (ref "J2") (pin "P3") (pinfunction "P3_P3") (pintype "passive"))
      (node (ref "J2") (pin "P4") (pinfunction "P4_P4") (pintype "passive"))
    )
    (net (code "47") (name "V_USB") (class "Default")
      (node (ref "C2") (pin "2") (pinfunction "2_2") (pintype "passive"))
      (node (ref "P1") (pin "7") (pinfunction "7_7") (pintype "passive"))
      (node (ref "R4") (pin "2") (pinfunction "2_2") (pintype "passive"))
      (node (ref "U1") (pin "13") (pinfunction "IN_13") (pintype "input"))
    )
    (net (code "48") (name "unconnected-(J2-MNT_1-Pad5)") (class "Default")
      (node (ref "J2") (pin "5") (pinfunction "MNT_1_5") (pintype "passive"))
    )
    (net (code "49") (name "unconnected-(J2-MNT_2-Pad6)") (class "Default")
      (node (ref "J2") (pin "6") (pinfunction "MNT_2_6") (pintype "passive"))
    )
    (net (code "50") (name "unconnected-(J2-MNT_3-Pad7)") (class "Default")
      (node (ref "J2") (pin "7") (pinfunction "MNT_3_7") (pintype "passive"))
    )
    (net (code "51") (name "unconnected-(J2-MNT_4-Pad8)") (class "Default")
      (node (ref "J2") (pin "8") (pinfunction "MNT_4_8") (pintype "passive"))
    )
    (net (code "52") (name "unconnected-(J3-Pad2)") (class "Default")
      (node (ref "J3") (pin "2") (pinfunction "2_2") (pintype "passive"))
    )
    (net (code "53") (name "unconnected-(J3-Pad3)") (class "Default")
      (node (ref "J3") (pin "3") (pinfunction "3_3") (pintype "passive"))
    )
    (net (code "54") (name "unconnected-(J3-Pad5)") (class "Default")
      (node (ref "J3") (pin "5") (pinfunction "5_5") (pintype "passive"))
    )
    (net (code "55") (name "unconnected-(J3-Pad10)") (class "Default")
      (node (ref "J3") (pin "10") (pinfunction "10_10") (pintype "passive"))
    )
    (net (code "56") (name "unconnected-(J4-Pad1)") (class "Default")
      (node (ref "J4") (pin "1") (pinfunction "1_1") (pintype "passive"))
    )
    (net (code "57") (name "unconnected-(J4-Pad6)") (class "Default")
      (node (ref "J4") (pin "6") (pinfunction "6_6") (pintype "passive"))
    )
    (net (code "58") (name "unconnected-(J4-Pad8)") (class "Default")
      (node (ref "J4") (pin "8") (pinfunction "8_8") (pintype "passive"))
    )
    (net (code "59") (name "unconnected-(J4-Pad9)") (class "Default")
      (node (ref "J4") (pin "9") (pinfunction "9_9") (pintype "passive"))
    )
    (net (code "60") (name "unconnected-(U1-TD-Pad15)") (class "Default")
      (node (ref "U1") (pin "15") (pinfunction "TD_15") (pintype "input"))
    )
    (net (code "61") (name "unconnected-(U1-TMR-Pad14)") (class "Default")
      (node (ref "U1") (pin "14") (pinfunction "TMR_14") (pintype "input"))
    )
    (net (code "62") (name "unconnected-(U3-CAP1_NC-Pad48)") (class "Default")
      (node (ref "U3") (pin "48") (pinfunction "CAP1_NC_48") (pintype "passive"))
    )
    (net (code "63") (name "unconnected-(U3-CAP2_NC-Pad47)") (class "Default")
      (node (ref "U3") (pin "47") (pinfunction "CAP2_NC_47") (pintype "passive"))
    )
    (net (code "64") (name "unconnected-(U3-CLK-Pad31)") (class "Default")
      (node (ref "U3") (pin "31") (pinfunction "CLK_31") (pintype "bidirectional"))
    )
    (net (code "65") (name "unconnected-(U3-CMD-Pad30)") (class "Default")
      (node (ref "U3") (pin "30") (pinfunction "CMD_30") (pintype "bidirectional"))
    )
    (net (code "66") (name "unconnected-(U3-IO2-Pad22)") (class "Default")
      (node (ref "U3") (pin "22") (pinfunction "IO2_22") (pintype "bidirectional"))
    )
    (net (code "67") (name "unconnected-(U3-IO12-Pad18)") (class "Default")
      (node (ref "U3") (pin "18") (pinfunction "IO12_18") (pintype "bidirectional"))
    )
    (net (code "68") (name "unconnected-(U3-IO13-Pad20)") (class "Default")
      (node (ref "U3") (pin "20") (pinfunction "IO13_20") (pintype "bidirectional"))
    )
    (net (code "69") (name "unconnected-(U3-IO14-Pad17)") (class "Default")
      (node (ref "U3") (pin "17") (pinfunction "IO14_17") (pintype "bidirectional"))
    )
    (net (code "70") (name "unconnected-(U3-IO16-Pad25)") (class "Default")
      (node (ref "U3") (pin "25") (pinfunction "IO16_25") (pintype "bidirectional"))
    )
    (net (code "71") (name "unconnected-(U3-IO17-Pad27)") (class "Default")
      (node (ref "U3") (pin "27") (pinfunction "IO17_27") (pintype "bidirectional"))
    )
    (net (code "72") (name "unconnected-(U3-IO19-Pad38)") (class "Default")
      (node (ref "U3") (pin "38") (pinfunction "IO19_38") (pintype "bidirectional"))
    )
    (net (code "73") (name "unconnected-(U3-IO25-Pad14)") (class "Default")
      (node (ref "U3") (pin "14") (pinfunction "IO25_14") (pintype "bidirectional"))
    )
    (net (code "74") (name "unconnected-(U3-IO26-Pad15)") (class "Default")
      (node (ref "U3") (pin "15") (pinfunction "IO26_15") (pintype "bidirectional"))
    )
    (net (code "75") (name "unconnected-(U3-IO27-Pad16)") (class "Default")
      (node (ref "U3") (pin "16") (pinfunction "IO27_16") (pintype "bidirectional"))
    )
    (net (code "76") (name "unconnected-(U3-IO32-Pad12)") (class "Default")
      (node (ref "U3") (pin "12") (pinfunction "IO32_12") (pintype "bidirectional"))
    )
    (net (code "77") (name "unconnected-(U3-IO33-Pad13)") (class "Default")
      (node (ref "U3") (pin "13") (pinfunction "IO33_13") (pintype "bidirectional"))
    )
    (net (code "78") (name "unconnected-(U3-IO34-Pad10)") (class "Default")
      (node (ref "U3") (pin "10") (pinfunction "IO34_10") (pintype "input"))
    )
    (net (code "79") (name "unconnected-(U3-IO35-Pad11)") (class "Default")
      (node (ref "U3") (pin "11") (pinfunction "IO35_11") (pintype "input"))
    )
    (net (code "80") (name "unconnected-(U3-SD0-Pad32)") (class "Default")
      (node (ref "U3") (pin "32") (pinfunction "SD0_32") (pintype "bidirectional"))
    )
    (net (code "81") (name "unconnected-(U3-SD1-Pad33)") (class "Default")
      (node (ref "U3") (pin "33") (pinfunction "SD1_33") (pintype "bidirectional"))
    )
    (net (code "82") (name "unconnected-(U3-SD2-Pad28)") (class "Default")
      (node (ref "U3") (pin "28") (pinfunction "SD2_28") (pintype "bidirectional"))
    )
    (net (code "83") (name "unconnected-(U3-SD3-Pad29)") (class "Default")
      (node (ref "U3") (pin "29") (pinfunction "SD3_29") (pintype "bidirectional"))
    )
    (net (code "84") (name "unconnected-(U3-SENSOR_CAPN-Pad7)") (class "Default")
      (node (ref "U3") (pin "7") (pinfunction "SENSOR_CAPN_7") (pintype "input"))
    )
    (net (code "85") (name "unconnected-(U3-SENSOR_CAPP-Pad6)") (class "Default")
      (node (ref "U3") (pin "6") (pinfunction "SENSOR_CAPP_6") (pintype "input"))
    )
    (net (code "86") (name "unconnected-(U3-SENSOR_VN-Pad8)") (class "Default")
      (node (ref "U3") (pin "8") (pinfunction "SENSOR_VN_8") (pintype "input"))
    )
    (net (code "87") (name "unconnected-(U3-SENSOR_VP-Pad5)") (class "Default")
      (node (ref "U3") (pin "5") (pinfunction "SENSOR_VP_5") (pintype "input"))
    )
    (net (code "88") (name "unconnected-(U3-VDD_SDIO-Pad26)") (class "Default")
      (node (ref "U3") (pin "26") (pinfunction "VDD_SDIO_26") (pintype "power_in"))
    )
    (net (code "89") (name "unconnected-(U3-XTAL_N_NC-Pad44)") (class "Default")
      (node (ref "U3") (pin "44") (pinfunction "XTAL_N_NC_44") (pintype "passive"))
    )
    (net (code "90") (name "unconnected-(U3-XTAL_P_NC-Pad45)") (class "Default")
      (node (ref "U3") (pin "45") (pinfunction "XTAL_P_NC_45") (pintype "passive"))
    )
    (net (code "91") (name "unconnected-(U5-DEN_A{slash}G-Pad13)") (class "Default")
      (node (ref "U5") (pin "13") (pinfunction "DEN_A/G_13") (pintype "input+no_connect"))
    )
    (net (code "92") (name "unconnected-(U5-DRDY_M-Pad9)") (class "Default")
      (node (ref "U5") (pin "9") (pinfunction "DRDY_M_9") (pintype "output"))
    )
    (net (code "93") (name "unconnected-(U5-INT1_A{slash}G-Pad11)") (class "Default")
      (node (ref "U5") (pin "11") (pinfunction "INT1_A/G_11") (pintype "output+no_connect"))
    )
    (net (code "94") (name "unconnected-(U5-INT2_A{slash}G-Pad12)") (class "Default")
      (node (ref "U5") (pin "12") (pinfunction "INT2_A/G_12") (pintype "output+no_connect"))
    )
    (net (code "95") (name "unconnected-(U5-INT_M-Pad10)") (class "Default")
      (node (ref "U5") (pin "10") (pinfunction "INT_M_10") (pintype "output"))
    )
    (net (code "96") (name "unconnected-(U5-RES-Pad14)") (class "Default")
      (node (ref "U5") (pin "14") (pinfunction "RES_14") (pintype "power_in+no_connect"))
    )
    (net (code "97") (name "unconnected-(U5-RES-Pad15)") (class "Default")
      (node (ref "U5") (pin "15") (pinfunction "RES_15") (pintype "power_in+no_connect"))
    )
    (net (code "98") (name "unconnected-(U5-RES-Pad16)") (class "Default")
      (node (ref "U5") (pin "16") (pinfunction "RES_16") (pintype "power_in+no_connect"))
    )
    (net (code "99") (name "unconnected-(U5-RES-Pad17)") (class "Default")
      (node (ref "U5") (pin "17") (pinfunction "RES_17") (pintype "power_in+no_connect"))
    )
    (net (code "100") (name "unconnected-(U5-RES-Pad18)") (class "Default")
      (node (ref "U5") (pin "18") (pinfunction "RES_18") (pintype "power_in+no_connect"))
    )
    (net (code "101") (name "unconnected-(U6-G_DRV-Pad7)") (class "Default")
      (node (ref "U6") (pin "7") (pinfunction "G_DRV_7") (pintype "input"))
    )
    (net (code "102") (name "unconnected-(U6-IR_DRV-Pad6)") (class "Default")
      (node (ref "U6") (pin "6") (pinfunction "IR_DRV_6") (pintype "input"))
    )
    (net (code "103") (name "unconnected-(U6-R_DRV-Pad5)") (class "Default")
      (node (ref "U6") (pin "5") (pinfunction "R_DRV_5") (pintype "input"))
    )
  )
)
